# BIT_2.net
KiCad netlist of a schematic drawn in EasyEDA
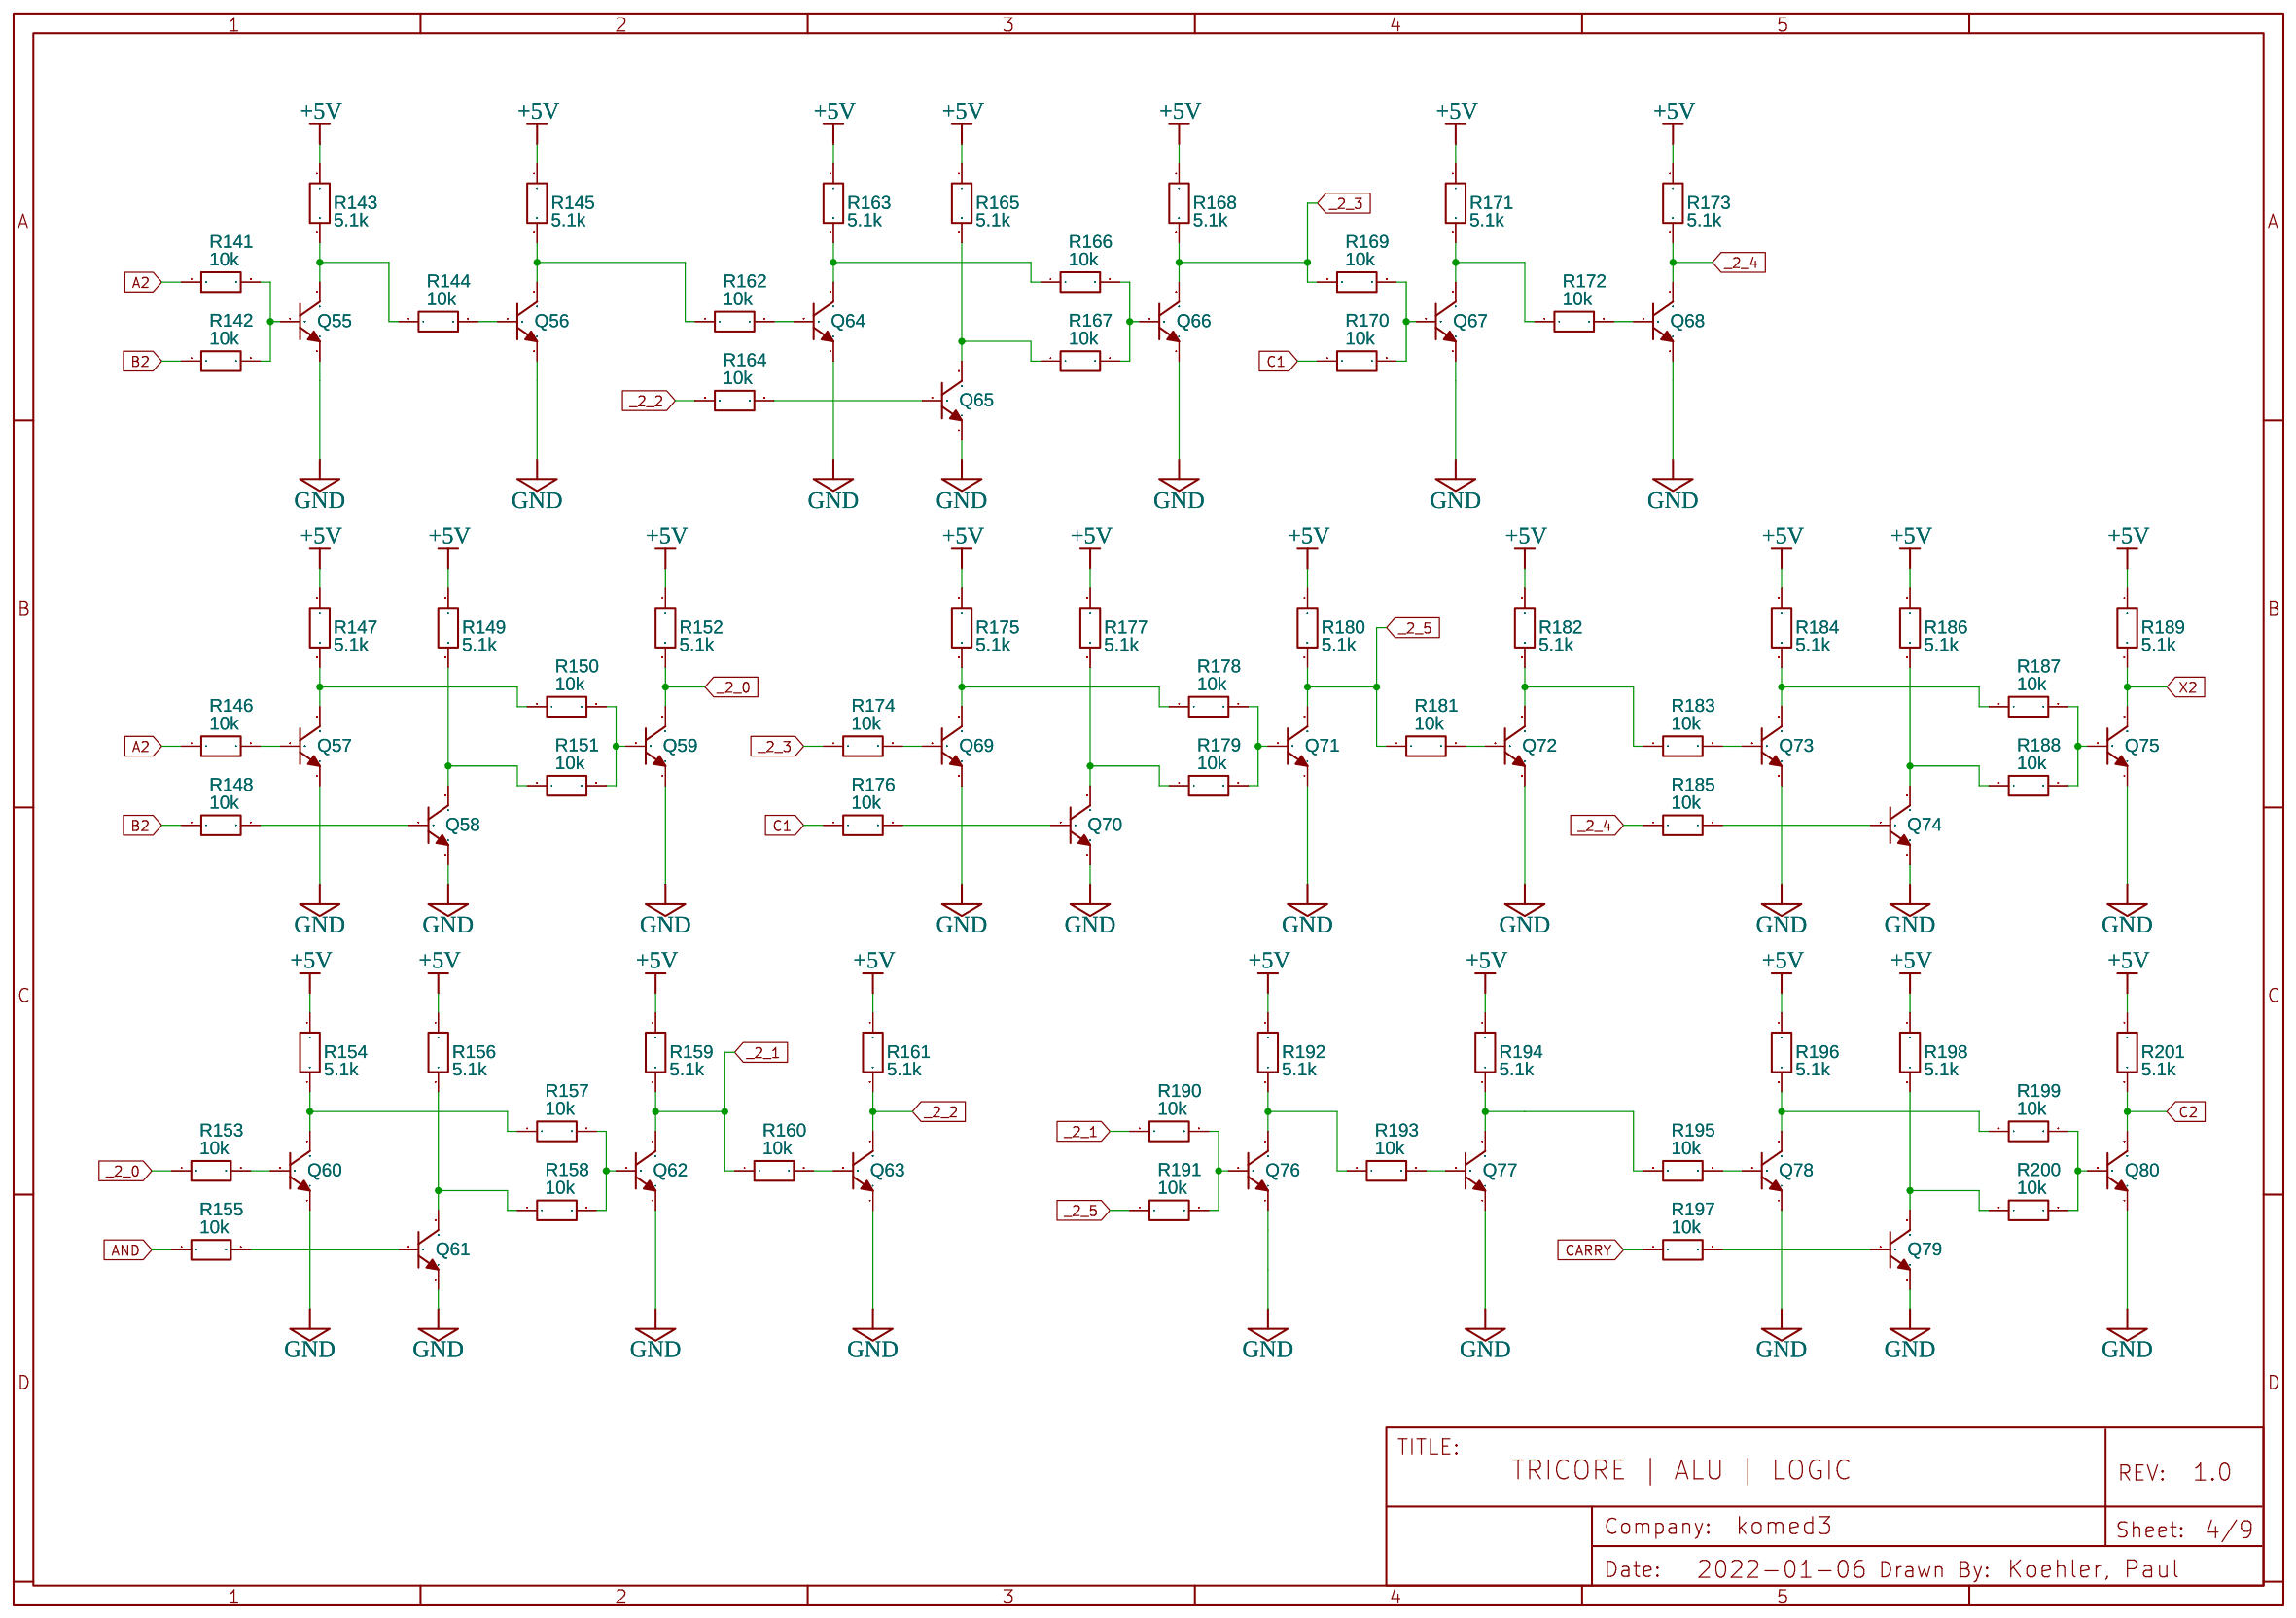
[diagram p0: schematic sheet]

(export (version "E")
  (design (tool "Eeschema 10.0.6"))
  (components
    (comp (ref "Q55")
      (value "2N3904(TO-92)")
      (fields (field (name "BOM_Manufacturer Part") "2N3904") (field (name "BOM_Supplier Part") "C118538"))
      (libsource (lib "") (part "2N3904(TO-92)"))
    )
    (comp (ref "Q56")
      (value "2N3904(TO-92)")
      (fields (field (name "BOM_Manufacturer Part") "2N3904") (field (name "BOM_Supplier Part") "C118538"))
      (libsource (lib "") (part "2N3904(TO-92)"))
    )
    (comp (ref "Q57")
      (value "2N3904(TO-92)")
      (fields (field (name "BOM_Manufacturer Part") "2N3904") (field (name "BOM_Supplier Part") "C118538"))
      (libsource (lib "") (part "2N3904(TO-92)"))
    )
    (comp (ref "Q58")
      (value "2N3904(TO-92)")
      (fields (field (name "BOM_Manufacturer Part") "2N3904") (field (name "BOM_Supplier Part") "C118538"))
      (libsource (lib "") (part "2N3904(TO-92)"))
    )
    (comp (ref "Q59")
      (value "2N3904(TO-92)")
      (fields (field (name "BOM_Manufacturer Part") "2N3904") (field (name "BOM_Supplier Part") "C118538"))
      (libsource (lib "") (part "2N3904(TO-92)"))
    )
    (comp (ref "Q60")
      (value "2N3904(TO-92)")
      (fields (field (name "BOM_Manufacturer Part") "2N3904") (field (name "BOM_Supplier Part") "C118538"))
      (libsource (lib "") (part "2N3904(TO-92)"))
    )
    (comp (ref "Q61")
      (value "2N3904(TO-92)")
      (fields (field (name "BOM_Manufacturer Part") "2N3904") (field (name "BOM_Supplier Part") "C118538"))
      (libsource (lib "") (part "2N3904(TO-92)"))
    )
    (comp (ref "Q62")
      (value "2N3904(TO-92)")
      (fields (field (name "BOM_Manufacturer Part") "2N3904") (field (name "BOM_Supplier Part") "C118538"))
      (libsource (lib "") (part "2N3904(TO-92)"))
    )
    (comp (ref "Q63")
      (value "2N3904(TO-92)")
      (fields (field (name "BOM_Manufacturer Part") "2N3904") (field (name "BOM_Supplier Part") "C118538"))
      (libsource (lib "") (part "2N3904(TO-92)"))
    )
    (comp (ref "Q64")
      (value "2N3904(TO-92)")
      (fields (field (name "BOM_Manufacturer Part") "2N3904") (field (name "BOM_Supplier Part") "C118538"))
      (libsource (lib "") (part "2N3904(TO-92)"))
    )
    (comp (ref "Q65")
      (value "2N3904(TO-92)")
      (fields (field (name "BOM_Manufacturer Part") "2N3904") (field (name "BOM_Supplier Part") "C118538"))
      (libsource (lib "") (part "2N3904(TO-92)"))
    )
    (comp (ref "Q66")
      (value "2N3904(TO-92)")
      (fields (field (name "BOM_Manufacturer Part") "2N3904") (field (name "BOM_Supplier Part") "C118538"))
      (libsource (lib "") (part "2N3904(TO-92)"))
    )
    (comp (ref "Q67")
      (value "2N3904(TO-92)")
      (fields (field (name "BOM_Manufacturer Part") "2N3904") (field (name "BOM_Supplier Part") "C118538"))
      (libsource (lib "") (part "2N3904(TO-92)"))
    )
    (comp (ref "Q68")
      (value "2N3904(TO-92)")
      (fields (field (name "BOM_Manufacturer Part") "2N3904") (field (name "BOM_Supplier Part") "C118538"))
      (libsource (lib "") (part "2N3904(TO-92)"))
    )
    (comp (ref "Q69")
      (value "2N3904(TO-92)")
      (fields (field (name "BOM_Manufacturer Part") "2N3904") (field (name "BOM_Supplier Part") "C118538"))
      (libsource (lib "") (part "2N3904(TO-92)"))
    )
    (comp (ref "Q70")
      (value "2N3904(TO-92)")
      (fields (field (name "BOM_Manufacturer Part") "2N3904") (field (name "BOM_Supplier Part") "C118538"))
      (libsource (lib "") (part "2N3904(TO-92)"))
    )
    (comp (ref "Q71")
      (value "2N3904(TO-92)")
      (fields (field (name "BOM_Manufacturer Part") "2N3904") (field (name "BOM_Supplier Part") "C118538"))
      (libsource (lib "") (part "2N3904(TO-92)"))
    )
    (comp (ref "Q72")
      (value "2N3904(TO-92)")
      (fields (field (name "BOM_Manufacturer Part") "2N3904") (field (name "BOM_Supplier Part") "C118538"))
      (libsource (lib "") (part "2N3904(TO-92)"))
    )
    (comp (ref "Q73")
      (value "2N3904(TO-92)")
      (fields (field (name "BOM_Manufacturer Part") "2N3904") (field (name "BOM_Supplier Part") "C118538"))
      (libsource (lib "") (part "2N3904(TO-92)"))
    )
    (comp (ref "Q74")
      (value "2N3904(TO-92)")
      (fields (field (name "BOM_Manufacturer Part") "2N3904") (field (name "BOM_Supplier Part") "C118538"))
      (libsource (lib "") (part "2N3904(TO-92)"))
    )
    (comp (ref "Q75")
      (value "2N3904(TO-92)")
      (fields (field (name "BOM_Manufacturer Part") "2N3904") (field (name "BOM_Supplier Part") "C118538"))
      (libsource (lib "") (part "2N3904(TO-92)"))
    )
    (comp (ref "Q76")
      (value "2N3904(TO-92)")
      (fields (field (name "BOM_Manufacturer Part") "2N3904") (field (name "BOM_Supplier Part") "C118538"))
      (libsource (lib "") (part "2N3904(TO-92)"))
    )
    (comp (ref "Q77")
      (value "2N3904(TO-92)")
      (fields (field (name "BOM_Manufacturer Part") "2N3904") (field (name "BOM_Supplier Part") "C118538"))
      (libsource (lib "") (part "2N3904(TO-92)"))
    )
    (comp (ref "Q78")
      (value "2N3904(TO-92)")
      (fields (field (name "BOM_Manufacturer Part") "2N3904") (field (name "BOM_Supplier Part") "C118538"))
      (libsource (lib "") (part "2N3904(TO-92)"))
    )
    (comp (ref "Q79")
      (value "2N3904(TO-92)")
      (fields (field (name "BOM_Manufacturer Part") "2N3904") (field (name "BOM_Supplier Part") "C118538"))
      (libsource (lib "") (part "2N3904(TO-92)"))
    )
    (comp (ref "Q80")
      (value "2N3904(TO-92)")
      (fields (field (name "BOM_Manufacturer Part") "2N3904") (field (name "BOM_Supplier Part") "C118538"))
      (libsource (lib "") (part "2N3904(TO-92)"))
    )
    (comp (ref "R141") (value "10k") (libsource (lib "") (part "R_AXIAL-0.3_EU_1")))
    (comp (ref "R142") (value "10k") (libsource (lib "") (part "R_AXIAL-0.3_EU_1")))
    (comp (ref "R143") (value "5.1k") (libsource (lib "") (part "R_AXIAL-0.3_EU")))
    (comp (ref "R144") (value "10k") (libsource (lib "") (part "R_AXIAL-0.3_EU_1")))
    (comp (ref "R145") (value "5.1k") (libsource (lib "") (part "R_AXIAL-0.3_EU")))
    (comp (ref "R146") (value "10k") (libsource (lib "") (part "R_AXIAL-0.3_EU_1")))
    (comp (ref "R147") (value "5.1k") (libsource (lib "") (part "R_AXIAL-0.3_EU")))
    (comp (ref "R148") (value "10k") (libsource (lib "") (part "R_AXIAL-0.3_EU_1")))
    (comp (ref "R149") (value "5.1k") (libsource (lib "") (part "R_AXIAL-0.3_EU")))
    (comp (ref "R150") (value "10k") (libsource (lib "") (part "R_AXIAL-0.3_EU_1")))
    (comp (ref "R151") (value "10k") (libsource (lib "") (part "R_AXIAL-0.3_EU_1")))
    (comp (ref "R152") (value "5.1k") (libsource (lib "") (part "R_AXIAL-0.3_EU")))
    (comp (ref "R153") (value "10k") (libsource (lib "") (part "R_AXIAL-0.3_EU_1")))
    (comp (ref "R154") (value "5.1k") (libsource (lib "") (part "R_AXIAL-0.3_EU")))
    (comp (ref "R155") (value "10k") (libsource (lib "") (part "R_AXIAL-0.3_EU_1")))
    (comp (ref "R156") (value "5.1k") (libsource (lib "") (part "R_AXIAL-0.3_EU")))
    (comp (ref "R157") (value "10k") (libsource (lib "") (part "R_AXIAL-0.3_EU_1")))
    (comp (ref "R158") (value "10k") (libsource (lib "") (part "R_AXIAL-0.3_EU_1")))
    (comp (ref "R159") (value "5.1k") (libsource (lib "") (part "R_AXIAL-0.3_EU")))
    (comp (ref "R160") (value "10k") (libsource (lib "") (part "R_AXIAL-0.3_EU_1")))
    (comp (ref "R161") (value "5.1k") (libsource (lib "") (part "R_AXIAL-0.3_EU")))
    (comp (ref "R162") (value "10k") (libsource (lib "") (part "R_AXIAL-0.3_EU_1")))
    (comp (ref "R163") (value "5.1k") (libsource (lib "") (part "R_AXIAL-0.3_EU")))
    (comp (ref "R164") (value "10k") (libsource (lib "") (part "R_AXIAL-0.3_EU_1")))
    (comp (ref "R165") (value "5.1k") (libsource (lib "") (part "R_AXIAL-0.3_EU")))
    (comp (ref "R166") (value "10k") (libsource (lib "") (part "R_AXIAL-0.3_EU_1")))
    (comp (ref "R167") (value "10k") (libsource (lib "") (part "R_AXIAL-0.3_EU_1")))
    (comp (ref "R168") (value "5.1k") (libsource (lib "") (part "R_AXIAL-0.3_EU")))
    (comp (ref "R169") (value "10k") (libsource (lib "") (part "R_AXIAL-0.3_EU_1")))
    (comp (ref "R170") (value "10k") (libsource (lib "") (part "R_AXIAL-0.3_EU_1")))
    (comp (ref "R171") (value "5.1k") (libsource (lib "") (part "R_AXIAL-0.3_EU")))
    (comp (ref "R172") (value "10k") (libsource (lib "") (part "R_AXIAL-0.3_EU_1")))
    (comp (ref "R173") (value "5.1k") (libsource (lib "") (part "R_AXIAL-0.3_EU")))
    (comp (ref "R174") (value "10k") (libsource (lib "") (part "R_AXIAL-0.3_EU_1")))
    (comp (ref "R175") (value "5.1k") (libsource (lib "") (part "R_AXIAL-0.3_EU")))
    (comp (ref "R176") (value "10k") (libsource (lib "") (part "R_AXIAL-0.3_EU_1")))
    (comp (ref "R177") (value "5.1k") (libsource (lib "") (part "R_AXIAL-0.3_EU")))
    (comp (ref "R178") (value "10k") (libsource (lib "") (part "R_AXIAL-0.3_EU_1")))
    (comp (ref "R179") (value "10k") (libsource (lib "") (part "R_AXIAL-0.3_EU_1")))
    (comp (ref "R180") (value "5.1k") (libsource (lib "") (part "R_AXIAL-0.3_EU")))
    (comp (ref "R181") (value "10k") (libsource (lib "") (part "R_AXIAL-0.3_EU_1")))
    (comp (ref "R182") (value "5.1k") (libsource (lib "") (part "R_AXIAL-0.3_EU")))
    (comp (ref "R183") (value "10k") (libsource (lib "") (part "R_AXIAL-0.3_EU_1")))
    (comp (ref "R184") (value "5.1k") (libsource (lib "") (part "R_AXIAL-0.3_EU")))
    (comp (ref "R185") (value "10k") (libsource (lib "") (part "R_AXIAL-0.3_EU_1")))
    (comp (ref "R186") (value "5.1k") (libsource (lib "") (part "R_AXIAL-0.3_EU")))
    (comp (ref "R187") (value "10k") (libsource (lib "") (part "R_AXIAL-0.3_EU_1")))
    (comp (ref "R188") (value "10k") (libsource (lib "") (part "R_AXIAL-0.3_EU_1")))
    (comp (ref "R189") (value "5.1k") (libsource (lib "") (part "R_AXIAL-0.3_EU")))
    (comp (ref "R190") (value "10k") (libsource (lib "") (part "R_AXIAL-0.3_EU_1")))
    (comp (ref "R191") (value "10k") (libsource (lib "") (part "R_AXIAL-0.3_EU_1")))
    (comp (ref "R192") (value "5.1k") (libsource (lib "") (part "R_AXIAL-0.3_EU")))
    (comp (ref "R193") (value "10k") (libsource (lib "") (part "R_AXIAL-0.3_EU_1")))
    (comp (ref "R194") (value "5.1k") (libsource (lib "") (part "R_AXIAL-0.3_EU")))
    (comp (ref "R195") (value "10k") (libsource (lib "") (part "R_AXIAL-0.3_EU_1")))
    (comp (ref "R196") (value "5.1k") (libsource (lib "") (part "R_AXIAL-0.3_EU")))
    (comp (ref "R197") (value "10k") (libsource (lib "") (part "R_AXIAL-0.3_EU_1")))
    (comp (ref "R198") (value "5.1k") (libsource (lib "") (part "R_AXIAL-0.3_EU")))
    (comp (ref "R199") (value "10k") (libsource (lib "") (part "R_AXIAL-0.3_EU_1")))
    (comp (ref "R200") (value "10k") (libsource (lib "") (part "R_AXIAL-0.3_EU_1")))
    (comp (ref "R201") (value "5.1k") (libsource (lib "") (part "R_AXIAL-0.3_EU")))
  )
  (nets
    (net (code "1") (name "+5V") (class "Default")
      (node (ref "R143") (pin "1") (pinfunction "1_1") (pintype "unspecified"))
      (node (ref "R145") (pin "1") (pinfunction "1_1") (pintype "unspecified"))
      (node (ref "R147") (pin "1") (pinfunction "1_1") (pintype "unspecified"))
      (node (ref "R149") (pin "1") (pinfunction "1_1") (pintype "unspecified"))
      (node (ref "R152") (pin "1") (pinfunction "1_1") (pintype "unspecified"))
      (node (ref "R154") (pin "1") (pinfunction "1_1") (pintype "unspecified"))
      (node (ref "R156") (pin "1") (pinfunction "1_1") (pintype "unspecified"))
      (node (ref "R159") (pin "1") (pinfunction "1_1") (pintype "unspecified"))
      (node (ref "R161") (pin "1") (pinfunction "1_1") (pintype "unspecified"))
      (node (ref "R163") (pin "1") (pinfunction "1_1") (pintype "unspecified"))
      (node (ref "R165") (pin "1") (pinfunction "1_1") (pintype "unspecified"))
      (node (ref "R168") (pin "1") (pinfunction "1_1") (pintype "unspecified"))
      (node (ref "R171") (pin "1") (pinfunction "1_1") (pintype "unspecified"))
      (node (ref "R173") (pin "1") (pinfunction "1_1") (pintype "unspecified"))
      (node (ref "R175") (pin "1") (pinfunction "1_1") (pintype "unspecified"))
      (node (ref "R177") (pin "1") (pinfunction "1_1") (pintype "unspecified"))
      (node (ref "R180") (pin "1") (pinfunction "1_1") (pintype "unspecified"))
      (node (ref "R182") (pin "1") (pinfunction "1_1") (pintype "unspecified"))
      (node (ref "R184") (pin "1") (pinfunction "1_1") (pintype "unspecified"))
      (node (ref "R186") (pin "1") (pinfunction "1_1") (pintype "unspecified"))
      (node (ref "R189") (pin "1") (pinfunction "1_1") (pintype "unspecified"))
      (node (ref "R192") (pin "1") (pinfunction "1_1") (pintype "unspecified"))
      (node (ref "R194") (pin "1") (pinfunction "1_1") (pintype "unspecified"))
      (node (ref "R196") (pin "1") (pinfunction "1_1") (pintype "unspecified"))
      (node (ref "R198") (pin "1") (pinfunction "1_1") (pintype "unspecified"))
      (node (ref "R201") (pin "1") (pinfunction "1_1") (pintype "unspecified"))
    )
    (net (code "2") (name "A2") (class "Default")
      (node (ref "R141") (pin "1") (pinfunction "1_1") (pintype "unspecified"))
      (node (ref "R146") (pin "1") (pinfunction "1_1") (pintype "unspecified"))
    )
    (net (code "3") (name "AND") (class "Default")
      (node (ref "R155") (pin "1") (pinfunction "1_1") (pintype "unspecified"))
    )
    (net (code "4") (name "B2") (class "Default")
      (node (ref "R142") (pin "1") (pinfunction "1_1") (pintype "unspecified"))
      (node (ref "R148") (pin "1") (pinfunction "1_1") (pintype "unspecified"))
    )
    (net (code "5") (name "C1") (class "Default")
      (node (ref "R170") (pin "1") (pinfunction "1_1") (pintype "unspecified"))
      (node (ref "R176") (pin "1") (pinfunction "1_1") (pintype "unspecified"))
    )
    (net (code "6") (name "C2") (class "Default")
      (node (ref "Q80") (pin "3") (pinfunction "C_3") (pintype "unspecified"))
      (node (ref "R201") (pin "2") (pinfunction "2_2") (pintype "unspecified"))
    )
    (net (code "7") (name "CARRY") (class "Default")
      (node (ref "R197") (pin "1") (pinfunction "1_1") (pintype "unspecified"))
    )
    (net (code "8") (name "GND") (class "Default")
      (node (ref "Q55") (pin "1") (pinfunction "E_1") (pintype "unspecified"))
      (node (ref "Q56") (pin "1") (pinfunction "E_1") (pintype "unspecified"))
      (node (ref "Q57") (pin "1") (pinfunction "E_1") (pintype "unspecified"))
      (node (ref "Q58") (pin "1") (pinfunction "E_1") (pintype "unspecified"))
      (node (ref "Q59") (pin "1") (pinfunction "E_1") (pintype "unspecified"))
      (node (ref "Q60") (pin "1") (pinfunction "E_1") (pintype "unspecified"))
      (node (ref "Q61") (pin "1") (pinfunction "E_1") (pintype "unspecified"))
      (node (ref "Q62") (pin "1") (pinfunction "E_1") (pintype "unspecified"))
      (node (ref "Q63") (pin "1") (pinfunction "E_1") (pintype "unspecified"))
      (node (ref "Q64") (pin "1") (pinfunction "E_1") (pintype "unspecified"))
      (node (ref "Q65") (pin "1") (pinfunction "E_1") (pintype "unspecified"))
      (node (ref "Q66") (pin "1") (pinfunction "E_1") (pintype "unspecified"))
      (node (ref "Q67") (pin "1") (pinfunction "E_1") (pintype "unspecified"))
      (node (ref "Q68") (pin "1") (pinfunction "E_1") (pintype "unspecified"))
      (node (ref "Q69") (pin "1") (pinfunction "E_1") (pintype "unspecified"))
      (node (ref "Q70") (pin "1") (pinfunction "E_1") (pintype "unspecified"))
      (node (ref "Q71") (pin "1") (pinfunction "E_1") (pintype "unspecified"))
      (node (ref "Q72") (pin "1") (pinfunction "E_1") (pintype "unspecified"))
      (node (ref "Q73") (pin "1") (pinfunction "E_1") (pintype "unspecified"))
      (node (ref "Q74") (pin "1") (pinfunction "E_1") (pintype "unspecified"))
      (node (ref "Q75") (pin "1") (pinfunction "E_1") (pintype "unspecified"))
      (node (ref "Q76") (pin "1") (pinfunction "E_1") (pintype "unspecified"))
      (node (ref "Q77") (pin "1") (pinfunction "E_1") (pintype "unspecified"))
      (node (ref "Q78") (pin "1") (pinfunction "E_1") (pintype "unspecified"))
      (node (ref "Q79") (pin "1") (pinfunction "E_1") (pintype "unspecified"))
      (node (ref "Q80") (pin "1") (pinfunction "E_1") (pintype "unspecified"))
    )
    (net (code "9") (name "Net-(Q55-B)") (class "Default")
      (node (ref "Q55") (pin "2") (pinfunction "B_2") (pintype "unspecified"))
      (node (ref "R141") (pin "2") (pinfunction "2_2") (pintype "unspecified"))
      (node (ref "R142") (pin "2") (pinfunction "2_2") (pintype "unspecified"))
    )
    (net (code "10") (name "Net-(Q55-C)") (class "Default")
      (node (ref "Q55") (pin "3") (pinfunction "C_3") (pintype "unspecified"))
      (node (ref "R143") (pin "2") (pinfunction "2_2") (pintype "unspecified"))
      (node (ref "R144") (pin "1") (pinfunction "1_1") (pintype "unspecified"))
    )
    (net (code "11") (name "Net-(Q56-B)") (class "Default")
      (node (ref "Q56") (pin "2") (pinfunction "B_2") (pintype "unspecified"))
      (node (ref "R144") (pin "2") (pinfunction "2_2") (pintype "unspecified"))
    )
    (net (code "12") (name "Net-(Q56-C)") (class "Default")
      (node (ref "Q56") (pin "3") (pinfunction "C_3") (pintype "unspecified"))
      (node (ref "R145") (pin "2") (pinfunction "2_2") (pintype "unspecified"))
      (node (ref "R162") (pin "1") (pinfunction "1_1") (pintype "unspecified"))
    )
    (net (code "13") (name "Net-(Q57-B)") (class "Default")
      (node (ref "Q57") (pin "2") (pinfunction "B_2") (pintype "unspecified"))
      (node (ref "R146") (pin "2") (pinfunction "2_2") (pintype "unspecified"))
    )
    (net (code "14") (name "Net-(Q57-C)") (class "Default")
      (node (ref "Q57") (pin "3") (pinfunction "C_3") (pintype "unspecified"))
      (node (ref "R147") (pin "2") (pinfunction "2_2") (pintype "unspecified"))
      (node (ref "R150") (pin "1") (pinfunction "1_1") (pintype "unspecified"))
    )
    (net (code "15") (name "Net-(Q58-B)") (class "Default")
      (node (ref "Q58") (pin "2") (pinfunction "B_2") (pintype "unspecified"))
      (node (ref "R148") (pin "2") (pinfunction "2_2") (pintype "unspecified"))
    )
    (net (code "16") (name "Net-(Q58-C)") (class "Default")
      (node (ref "Q58") (pin "3") (pinfunction "C_3") (pintype "unspecified"))
      (node (ref "R149") (pin "2") (pinfunction "2_2") (pintype "unspecified"))
      (node (ref "R151") (pin "1") (pinfunction "1_1") (pintype "unspecified"))
    )
    (net (code "17") (name "Net-(Q59-B)") (class "Default")
      (node (ref "Q59") (pin "2") (pinfunction "B_2") (pintype "unspecified"))
      (node (ref "R150") (pin "2") (pinfunction "2_2") (pintype "unspecified"))
      (node (ref "R151") (pin "2") (pinfunction "2_2") (pintype "unspecified"))
    )
    (net (code "18") (name "Net-(Q60-B)") (class "Default")
      (node (ref "Q60") (pin "2") (pinfunction "B_2") (pintype "unspecified"))
      (node (ref "R153") (pin "2") (pinfunction "2_2") (pintype "unspecified"))
    )
    (net (code "19") (name "Net-(Q60-C)") (class "Default")
      (node (ref "Q60") (pin "3") (pinfunction "C_3") (pintype "unspecified"))
      (node (ref "R154") (pin "2") (pinfunction "2_2") (pintype "unspecified"))
      (node (ref "R157") (pin "1") (pinfunction "1_1") (pintype "unspecified"))
    )
    (net (code "20") (name "Net-(Q61-B)") (class "Default")
      (node (ref "Q61") (pin "2") (pinfunction "B_2") (pintype "unspecified"))
      (node (ref "R155") (pin "2") (pinfunction "2_2") (pintype "unspecified"))
    )
    (net (code "21") (name "Net-(Q61-C)") (class "Default")
      (node (ref "Q61") (pin "3") (pinfunction "C_3") (pintype "unspecified"))
      (node (ref "R156") (pin "2") (pinfunction "2_2") (pintype "unspecified"))
      (node (ref "R158") (pin "1") (pinfunction "1_1") (pintype "unspecified"))
    )
    (net (code "22") (name "Net-(Q62-B)") (class "Default")
      (node (ref "Q62") (pin "2") (pinfunction "B_2") (pintype "unspecified"))
      (node (ref "R157") (pin "2") (pinfunction "2_2") (pintype "unspecified"))
      (node (ref "R158") (pin "2") (pinfunction "2_2") (pintype "unspecified"))
    )
    (net (code "23") (name "Net-(Q63-B)") (class "Default")
      (node (ref "Q63") (pin "2") (pinfunction "B_2") (pintype "unspecified"))
      (node (ref "R160") (pin "2") (pinfunction "2_2") (pintype "unspecified"))
    )
    (net (code "24") (name "Net-(Q64-B)") (class "Default")
      (node (ref "Q64") (pin "2") (pinfunction "B_2") (pintype "unspecified"))
      (node (ref "R162") (pin "2") (pinfunction "2_2") (pintype "unspecified"))
    )
    (net (code "25") (name "Net-(Q64-C)") (class "Default")
      (node (ref "Q64") (pin "3") (pinfunction "C_3") (pintype "unspecified"))
      (node (ref "R163") (pin "2") (pinfunction "2_2") (pintype "unspecified"))
      (node (ref "R166") (pin "1") (pinfunction "1_1") (pintype "unspecified"))
    )
    (net (code "26") (name "Net-(Q65-B)") (class "Default")
      (node (ref "Q65") (pin "2") (pinfunction "B_2") (pintype "unspecified"))
      (node (ref "R164") (pin "2") (pinfunction "2_2") (pintype "unspecified"))
    )
    (net (code "27") (name "Net-(Q65-C)") (class "Default")
      (node (ref "Q65") (pin "3") (pinfunction "C_3") (pintype "unspecified"))
      (node (ref "R165") (pin "2") (pinfunction "2_2") (pintype "unspecified"))
      (node (ref "R167") (pin "1") (pinfunction "1_1") (pintype "unspecified"))
    )
    (net (code "28") (name "Net-(Q66-B)") (class "Default")
      (node (ref "Q66") (pin "2") (pinfunction "B_2") (pintype "unspecified"))
      (node (ref "R166") (pin "2") (pinfunction "2_2") (pintype "unspecified"))
      (node (ref "R167") (pin "2") (pinfunction "2_2") (pintype "unspecified"))
    )
    (net (code "29") (name "Net-(Q67-B)") (class "Default")
      (node (ref "Q67") (pin "2") (pinfunction "B_2") (pintype "unspecified"))
      (node (ref "R169") (pin "2") (pinfunction "2_2") (pintype "unspecified"))
      (node (ref "R170") (pin "2") (pinfunction "2_2") (pintype "unspecified"))
    )
    (net (code "30") (name "Net-(Q67-C)") (class "Default")
      (node (ref "Q67") (pin "3") (pinfunction "C_3") (pintype "unspecified"))
      (node (ref "R171") (pin "2") (pinfunction "2_2") (pintype "unspecified"))
      (node (ref "R172") (pin "1") (pinfunction "1_1") (pintype "unspecified"))
    )
    (net (code "31") (name "Net-(Q68-B)") (class "Default")
      (node (ref "Q68") (pin "2") (pinfunction "B_2") (pintype "unspecified"))
      (node (ref "R172") (pin "2") (pinfunction "2_2") (pintype "unspecified"))
    )
    (net (code "32") (name "Net-(Q69-B)") (class "Default")
      (node (ref "Q69") (pin "2") (pinfunction "B_2") (pintype "unspecified"))
      (node (ref "R174") (pin "2") (pinfunction "2_2") (pintype "unspecified"))
    )
    (net (code "33") (name "Net-(Q69-C)") (class "Default")
      (node (ref "Q69") (pin "3") (pinfunction "C_3") (pintype "unspecified"))
      (node (ref "R175") (pin "2") (pinfunction "2_2") (pintype "unspecified"))
      (node (ref "R178") (pin "1") (pinfunction "1_1") (pintype "unspecified"))
    )
    (net (code "34") (name "Net-(Q70-B)") (class "Default")
      (node (ref "Q70") (pin "2") (pinfunction "B_2") (pintype "unspecified"))
      (node (ref "R176") (pin "2") (pinfunction "2_2") (pintype "unspecified"))
    )
    (net (code "35") (name "Net-(Q70-C)") (class "Default")
      (node (ref "Q70") (pin "3") (pinfunction "C_3") (pintype "unspecified"))
      (node (ref "R177") (pin "2") (pinfunction "2_2") (pintype "unspecified"))
      (node (ref "R179") (pin "1") (pinfunction "1_1") (pintype "unspecified"))
    )
    (net (code "36") (name "Net-(Q71-B)") (class "Default")
      (node (ref "Q71") (pin "2") (pinfunction "B_2") (pintype "unspecified"))
      (node (ref "R178") (pin "2") (pinfunction "2_2") (pintype "unspecified"))
      (node (ref "R179") (pin "2") (pinfunction "2_2") (pintype "unspecified"))
    )
    (net (code "37") (name "Net-(Q72-B)") (class "Default")
      (node (ref "Q72") (pin "2") (pinfunction "B_2") (pintype "unspecified"))
      (node (ref "R181") (pin "2") (pinfunction "2_2") (pintype "unspecified"))
    )
    (net (code "38") (name "Net-(Q72-C)") (class "Default")
      (node (ref "Q72") (pin "3") (pinfunction "C_3") (pintype "unspecified"))
      (node (ref "R182") (pin "2") (pinfunction "2_2") (pintype "unspecified"))
      (node (ref "R183") (pin "1") (pinfunction "1_1") (pintype "unspecified"))
    )
    (net (code "39") (name "Net-(Q73-B)") (class "Default")
      (node (ref "Q73") (pin "2") (pinfunction "B_2") (pintype "unspecified"))
      (node (ref "R183") (pin "2") (pinfunction "2_2") (pintype "unspecified"))
    )
    (net (code "40") (name "Net-(Q73-C)") (class "Default")
      (node (ref "Q73") (pin "3") (pinfunction "C_3") (pintype "unspecified"))
      (node (ref "R184") (pin "2") (pinfunction "2_2") (pintype "unspecified"))
      (node (ref "R187") (pin "1") (pinfunction "1_1") (pintype "unspecified"))
    )
    (net (code "41") (name "Net-(Q74-B)") (class "Default")
      (node (ref "Q74") (pin "2") (pinfunction "B_2") (pintype "unspecified"))
      (node (ref "R185") (pin "2") (pinfunction "2_2") (pintype "unspecified"))
    )
    (net (code "42") (name "Net-(Q74-C)") (class "Default")
      (node (ref "Q74") (pin "3") (pinfunction "C_3") (pintype "unspecified"))
      (node (ref "R186") (pin "2") (pinfunction "2_2") (pintype "unspecified"))
      (node (ref "R188") (pin "1") (pinfunction "1_1") (pintype "unspecified"))
    )
    (net (code "43") (name "Net-(Q75-B)") (class "Default")
      (node (ref "Q75") (pin "2") (pinfunction "B_2") (pintype "unspecified"))
      (node (ref "R187") (pin "2") (pinfunction "2_2") (pintype "unspecified"))
      (node (ref "R188") (pin "2") (pinfunction "2_2") (pintype "unspecified"))
    )
    (net (code "44") (name "Net-(Q76-B)") (class "Default")
      (node (ref "Q76") (pin "2") (pinfunction "B_2") (pintype "unspecified"))
      (node (ref "R190") (pin "2") (pinfunction "2_2") (pintype "unspecified"))
      (node (ref "R191") (pin "2") (pinfunction "2_2") (pintype "unspecified"))
    )
    (net (code "45") (name "Net-(Q76-C)") (class "Default")
      (node (ref "Q76") (pin "3") (pinfunction "C_3") (pintype "unspecified"))
      (node (ref "R192") (pin "2") (pinfunction "2_2") (pintype "unspecified"))
      (node (ref "R193") (pin "1") (pinfunction "1_1") (pintype "unspecified"))
    )
    (net (code "46") (name "Net-(Q77-B)") (class "Default")
      (node (ref "Q77") (pin "2") (pinfunction "B_2") (pintype "unspecified"))
      (node (ref "R193") (pin "2") (pinfunction "2_2") (pintype "unspecified"))
    )
    (net (code "47") (name "Net-(Q77-C)") (class "Default")
      (node (ref "Q77") (pin "3") (pinfunction "C_3") (pintype "unspecified"))
      (node (ref "R194") (pin "2") (pinfunction "2_2") (pintype "unspecified"))
      (node (ref "R195") (pin "1") (pinfunction "1_1") (pintype "unspecified"))
    )
    (net (code "48") (name "Net-(Q78-B)") (class "Default")
      (node (ref "Q78") (pin "2") (pinfunction "B_2") (pintype "unspecified"))
      (node (ref "R195") (pin "2") (pinfunction "2_2") (pintype "unspecified"))
    )
    (net (code "49") (name "Net-(Q78-C)") (class "Default")
      (node (ref "Q78") (pin "3") (pinfunction "C_3") (pintype "unspecified"))
      (node (ref "R196") (pin "2") (pinfunction "2_2") (pintype "unspecified"))
      (node (ref "R199") (pin "1") (pinfunction "1_1") (pintype "unspecified"))
    )
    (net (code "50") (name "Net-(Q79-B)") (class "Default")
      (node (ref "Q79") (pin "2") (pinfunction "B_2") (pintype "unspecified"))
      (node (ref "R197") (pin "2") (pinfunction "2_2") (pintype "unspecified"))
    )
    (net (code "51") (name "Net-(Q79-C)") (class "Default")
      (node (ref "Q79") (pin "3") (pinfunction "C_3") (pintype "unspecified"))
      (node (ref "R198") (pin "2") (pinfunction "2_2") (pintype "unspecified"))
      (node (ref "R200") (pin "1") (pinfunction "1_1") (pintype "unspecified"))
    )
    (net (code "52") (name "Net-(Q80-B)") (class "Default")
      (node (ref "Q80") (pin "2") (pinfunction "B_2") (pintype "unspecified"))
      (node (ref "R199") (pin "2") (pinfunction "2_2") (pintype "unspecified"))
      (node (ref "R200") (pin "2") (pinfunction "2_2") (pintype "unspecified"))
    )
    (net (code "53") (name "X2") (class "Default")
      (node (ref "Q75") (pin "3") (pinfunction "C_3") (pintype "unspecified"))
      (node (ref "R189") (pin "2") (pinfunction "2_2") (pintype "unspecified"))
    )
    (net (code "54") (name "_2_0") (class "Default")
      (node (ref "Q59") (pin "3") (pinfunction "C_3") (pintype "unspecified"))
      (node (ref "R152") (pin "2") (pinfunction "2_2") (pintype "unspecified"))
      (node (ref "R153") (pin "1") (pinfunction "1_1") (pintype "unspecified"))
    )
    (net (code "55") (name "_2_1") (class "Default")
      (node (ref "Q62") (pin "3") (pinfunction "C_3") (pintype "unspecified"))
      (node (ref "R159") (pin "2") (pinfunction "2_2") (pintype "unspecified"))
      (node (ref "R160") (pin "1") (pinfunction "1_1") (pintype "unspecified"))
      (node (ref "R190") (pin "1") (pinfunction "1_1") (pintype "unspecified"))
    )
    (net (code "56") (name "_2_2") (class "Default")
      (node (ref "Q63") (pin "3") (pinfunction "C_3") (pintype "unspecified"))
      (node (ref "R161") (pin "2") (pinfunction "2_2") (pintype "unspecified"))
      (node (ref "R164") (pin "1") (pinfunction "1_1") (pintype "unspecified"))
    )
    (net (code "57") (name "_2_3") (class "Default")
      (node (ref "Q66") (pin "3") (pinfunction "C_3") (pintype "unspecified"))
      (node (ref "R168") (pin "2") (pinfunction "2_2") (pintype "unspecified"))
      (node (ref "R169") (pin "1") (pinfunction "1_1") (pintype "unspecified"))
      (node (ref "R174") (pin "1") (pinfunction "1_1") (pintype "unspecified"))
    )
    (net (code "58") (name "_2_4") (class "Default")
      (node (ref "Q68") (pin "3") (pinfunction "C_3") (pintype "unspecified"))
      (node (ref "R173") (pin "2") (pinfunction "2_2") (pintype "unspecified"))
      (node (ref "R185") (pin "1") (pinfunction "1_1") (pintype "unspecified"))
    )
    (net (code "59") (name "_2_5") (class "Default")
      (node (ref "Q71") (pin "3") (pinfunction "C_3") (pintype "unspecified"))
      (node (ref "R180") (pin "2") (pinfunction "2_2") (pintype "unspecified"))
      (node (ref "R181") (pin "1") (pinfunction "1_1") (pintype "unspecified"))
      (node (ref "R191") (pin "1") (pinfunction "1_1") (pintype "unspecified"))
    )
  )
)
